# Motor-X.net
KiCad netlist of a schematic drawn in Altium Designer
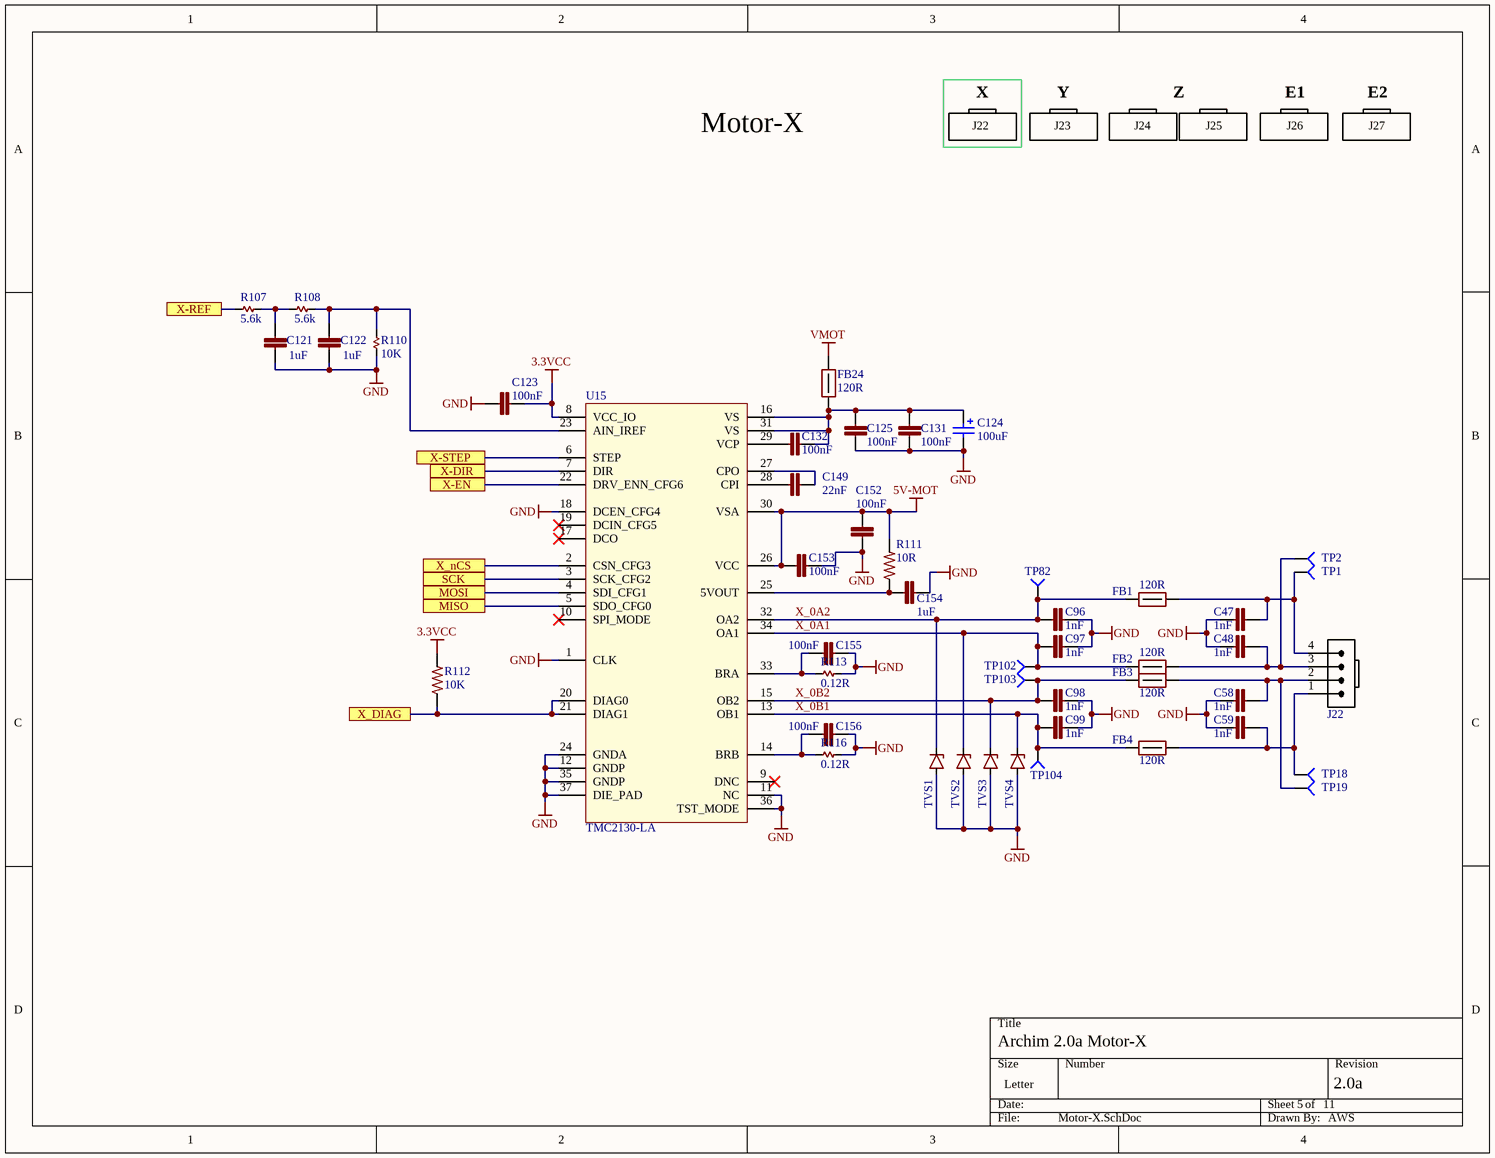
[diagram p0: Motor-X.SchDoc]

(export (version "E")
  (design (tool "Eeschema 10.0.6"))
  (components
    (comp (ref "C47")
      (value "1nF")
      (footprint "C0402")
      (description "1000pF 50V Ceramic Capacitor X7R 0402 (1005 Metric) 0.039\" L x 0.020\" W (1.00mm x 0.50mm)")
      (fields (field (name "MANUFACTURER") "Murata") (field (name "PART") "1nF 50V X7R 0402"))
      (libsource (lib "3Delight") (part "CAP 1nF 50V 0402 X7R"))
    )
    (comp (ref "C48")
      (value "1nF")
      (footprint "C0402")
      (description "1000pF 50V Ceramic Capacitor X7R 0402 (1005 Metric) 0.039\" L x 0.020\" W (1.00mm x 0.50mm)")
      (fields (field (name "MANUFACTURER") "Murata") (field (name "PART") "1nF 50V X7R 0402"))
      (libsource (lib "3Delight") (part "CAP 1nF 50V 0402 X7R"))
    )
    (comp (ref "C58")
      (value "1nF")
      (footprint "C0402")
      (description "1000pF 50V Ceramic Capacitor X7R 0402 (1005 Metric) 0.039\" L x 0.020\" W (1.00mm x 0.50mm)")
      (fields (field (name "MANUFACTURER") "Murata") (field (name "PART") "1nF 50V X7R 0402"))
      (libsource (lib "3Delight") (part "CAP 1nF 50V 0402 X7R"))
    )
    (comp (ref "C59")
      (value "1nF")
      (footprint "C0402")
      (description "1000pF 50V Ceramic Capacitor X7R 0402 (1005 Metric) 0.039\" L x 0.020\" W (1.00mm x 0.50mm)")
      (fields (field (name "MANUFACTURER") "Murata") (field (name "PART") "1nF 50V X7R 0402"))
      (libsource (lib "3Delight") (part "CAP 1nF 50V 0402 X7R"))
    )
    (comp (ref "C96")
      (value "1nF")
      (footprint "C0402")
      (description "1000pF 50V Ceramic Capacitor X7R 0402 (1005 Metric) 0.039\" L x 0.020\" W (1.00mm x 0.50mm)")
      (fields (field (name "MANUFACTURER") "Murata") (field (name "PART") "1nF 50V X7R 0402"))
      (libsource (lib "3Delight") (part "CAP 1nF 50V 0402 X7R"))
    )
    (comp (ref "C97")
      (value "1nF")
      (footprint "C0402")
      (description "1000pF 50V Ceramic Capacitor X7R 0402 (1005 Metric) 0.039\" L x 0.020\" W (1.00mm x 0.50mm)")
      (fields (field (name "MANUFACTURER") "Murata") (field (name "PART") "1nF 50V X7R 0402"))
      (libsource (lib "3Delight") (part "CAP 1nF 50V 0402 X7R"))
    )
    (comp (ref "C98")
      (value "1nF")
      (footprint "C0402")
      (description "1000pF 50V Ceramic Capacitor X7R 0402 (1005 Metric) 0.039\" L x 0.020\" W (1.00mm x 0.50mm)")
      (fields (field (name "MANUFACTURER") "Murata") (field (name "PART") "1nF 50V X7R 0402"))
      (libsource (lib "3Delight") (part "CAP 1nF 50V 0402 X7R"))
    )
    (comp (ref "C99")
      (value "1nF")
      (footprint "C0402")
      (description "1000pF 50V Ceramic Capacitor X7R 0402 (1005 Metric) 0.039\" L x 0.020\" W (1.00mm x 0.50mm)")
      (fields (field (name "MANUFACTURER") "Murata") (field (name "PART") "1nF 50V X7R 0402"))
      (libsource (lib "3Delight") (part "CAP 1nF 50V 0402 X7R"))
    )
    (comp (ref "C121")
      (value "1uF")
      (footprint "C0402")
      (description "CAP CER 0402 1uF 6.3V 10% X5R")
      (fields (field (name "MANUFACTURER") "Murata") (field (name "PART") "1uF 6.3V X5R 0402"))
      (libsource (lib "3Delight") (part "GRM155R60J105KE19D"))
    )
    (comp (ref "C122")
      (value "1uF")
      (footprint "C0402")
      (description "CAP CER 0402 1uF 6.3V 10% X5R")
      (fields (field (name "MANUFACTURER") "Murata") (field (name "PART") "1uF 6.3V X5R 0402"))
      (libsource (lib "3Delight") (part "GRM155R60J105KE19D"))
    )
    (comp (ref "C123")
      (value "100nF")
      (footprint "C0402")
      (description "CAP CER 0402 100nF 16V 10% X7R")
      (fields (field (name "MANUFACTURER") "Murata") (field (name "PART") "0.1uF 16V X7R 0402"))
      (libsource (lib "3Delight") (part "GRM155R71C104KA88D"))
    )
    (comp (ref "C124")
      (value "100uF")
      (footprint "CAP-ELEC-063063077")
      (description "CAP ALUM 100UF 35V 20% SMD")
      (fields (field (name "MANUFACTURER") "Nichicon") (field (name "PART") "100uF 35V SMD Al-El"))
      (libsource (lib "3Delight") (part "UWT1V101MCL1GS"))
    )
    (comp (ref "C125")
      (value "100nF")
      (footprint "C0603")
      (description "CAP CER 0603 100nF 50V 10% X7R")
      (fields (field (name "MANUFACTURER") "Kemet") (field (name "PART") "100nF 50V X7R 0603"))
      (libsource (lib "") (part "C0603C104K5RACTU_1"))
    )
    (comp (ref "C131")
      (value "100nF")
      (footprint "C0603")
      (description "CAP CER 0603 100nF 50V 10% X7R")
      (fields (field (name "MANUFACTURER") "Kemet") (field (name "PART") "100nF 50V X7R 0603"))
      (libsource (lib "") (part "C0603C104K5RACTU_1"))
    )
    (comp (ref "C132")
      (value "100nF")
      (footprint "C0603")
      (description "CAP CER 0603 100nF 50V 10% X7R")
      (fields (field (name "MANUFACTURER") "Kemet") (field (name "PART") "100nF 50V X7R 0603"))
      (libsource (lib "") (part "C0603C104K5RACTU_2"))
    )
    (comp (ref "C149")
      (value "22nF")
      (footprint "C0402")
      (description "CAP CER 0402 22nF ±10% 50V X7R")
      (fields (field (name "MANUFACTURER") "YAGEO") (field (name "TOLERANCE") "+/- 10%"))
      (libsource (lib "3Delight") (part "GCM155R71H223KA55D"))
    )
    (comp (ref "C152")
      (value "100nF")
      (footprint "C0402")
      (description "CAP CER 0402 100nF 16V 10% X7R")
      (fields (field (name "MANUFACTURER") "Murata") (field (name "PART") "0.1uF 16V X7R 0402"))
      (libsource (lib "") (part "GRM155R71C104KA88D_1"))
    )
    (comp (ref "C153")
      (value "100nF")
      (footprint "C0402")
      (description "CAP CER 0402 100nF 16V 10% X7R")
      (fields (field (name "MANUFACTURER") "Murata") (field (name "PART") "0.1uF 16V X7R 0402"))
      (libsource (lib "3Delight") (part "GRM155R71C104KA88D"))
    )
    (comp (ref "C154")
      (value "1uF")
      (footprint "C0402")
      (description "CAP CER 0402 1uF 6.3V 10% X5R")
      (fields (field (name "MANUFACTURER") "Murata") (field (name "PART") "1uF 6.3V X5R 0402"))
      (libsource (lib "") (part "GRM155R60J105KE19D_1"))
    )
    (comp (ref "C155")
      (value "100nF")
      (footprint "C0603")
      (description "CAP CER 0603 100nF 50V 10% X7R")
      (fields (field (name "MANUFACTURER") "Kemet") (field (name "PART") "100nF 50V X7R 0603"))
      (libsource (lib "3Delight") (part "C0603C104K5RACTU"))
    )
    (comp (ref "C156")
      (value "100nF")
      (footprint "C0603")
      (description "CAP CER 0603 100nF 50V 10% X7R")
      (fields (field (name "MANUFACTURER") "Kemet") (field (name "PART") "100nF 50V X7R 0603"))
      (libsource (lib "3Delight") (part "C0603C104K5RACTU"))
    )
    (comp (ref "FB1")
      (value "120R")
      (footprint "FB0603")
      (description "FERRITE BEAD 120 OHM 0603 1LN")
      (fields (field (name "MANUFACTURER") "Samsung") (field (name "PART") "FERRITE 120R 3A 0603"))
      (libsource (lib "3Delight") (part "FERRITE 220R 2.5A 0603"))
    )
    (comp (ref "FB2")
      (value "120R")
      (footprint "FB0603")
      (description "FERRITE BEAD 120 OHM 0603 1LN")
      (fields (field (name "MANUFACTURER") "Samsung") (field (name "PART") "FERRITE 120R 3A 0603"))
      (libsource (lib "3Delight") (part "FERRITE 220R 2.5A 0603"))
    )
    (comp (ref "FB3")
      (value "120R")
      (footprint "FB0603")
      (description "FERRITE BEAD 120 OHM 0603 1LN")
      (fields (field (name "MANUFACTURER") "Samsung") (field (name "PART") "FERRITE 120R 3A 0603"))
      (libsource (lib "3Delight") (part "FERRITE 220R 2.5A 0603"))
    )
    (comp (ref "FB4")
      (value "120R")
      (footprint "FB0603")
      (description "FERRITE BEAD 120 OHM 0603 1LN")
      (fields (field (name "MANUFACTURER") "Samsung") (field (name "PART") "FERRITE 120R 3A 0603"))
      (libsource (lib "3Delight") (part "FERRITE 220R 2.5A 0603"))
    )
    (comp (ref "FB24")
      (value "120R")
      (footprint "FB0603")
      (description "FERRITE BEAD 120 OHM 0603 1LN")
      (fields (field (name "MANUFACTURER") "Samsung") (field (name "PART") "FERRITE 120R 3A 0603"))
      (libsource (lib "Inductors") (part "FERRITE 120R 3A 0603"))
    )
    (comp (ref "J22")
      (value "Molex 0705430038")
      (footprint "4POL254 PIN-IN-PASTE")
      (description "Molex 4 Pin Clip Connector - Pin In Paste footprint")
      (libsource (lib "Connectors") (part "Molex 0705430003 PIP"))
    )
    (comp (ref "R107")
      (value "5.6k")
      (footprint "R0402")
      (description "RES SMD 5.6K OHM 1% 1/16W 0402")
      (fields (field (name "MANUFACTURER") "YAGEO") (field (name "TOLERANCE") "1%"))
      (libsource (lib "Resistors") (part "5.6k 1% 0402"))
    )
    (comp (ref "R108")
      (value "5.6k")
      (footprint "R0402")
      (description "RES SMD 5.6K OHM 1% 1/16W 0402")
      (fields (field (name "MANUFACTURER") "YAGEO") (field (name "TOLERANCE") "1%"))
      (libsource (lib "Resistors") (part "5.6k 1% 0402"))
    )
    (comp (ref "R110")
      (value "10K")
      (footprint "R0402")
      (description "RES SMD 10K OHM 1% 1/16W 0402")
      (fields (field (name "MANUFACTURER") "Yageo") (field (name "PART") "10k 1% 0402"))
      (libsource (lib "Resistors") (part "10k 1% 0402"))
    )
    (comp (ref "R111")
      (value "10R")
      (footprint "R0402")
      (description "RES SMD 10 OHM 1% 1/16W 0402")
      (fields (field (name "MANUFACTURER") "Yageo") (field (name "TOLERANCE") "1%"))
      (libsource (lib "3Delight") (part "RC0402FR-0710RL"))
    )
    (comp (ref "R112")
      (value "10K")
      (footprint "R0402")
      (description "RES SMD 10K OHM 1% 1/16W 0402")
      (fields (field (name "MANUFACTURER") "Yageo") (field (name "PART") "10k 1% 0402"))
      (libsource (lib "3Delight") (part "RC0402FR-0710KP"))
    )
    (comp (ref "R113")
      (value "0.12R")
      (footprint "R1206")
      (description "RES 0.12 OHM 1% 1/2W 1206")
      (fields (field (name "TOLERANCE") "+/- 1%"))
      (libsource (lib "Resistors") (part "0.12R 1% 1206"))
    )
    (comp (ref "R116")
      (value "0.12R")
      (footprint "R1206")
      (description "RES 0.12 OHM 1% 1/2W 1206")
      (fields (field (name "TOLERANCE") "+/- 1%"))
      (libsource (lib "Resistors") (part "0.12R 1% 1206"))
    )
    (comp (ref "TP1")
      (value "TP4")
      (footprint "TP-2")
      (description "Socket")
      (libsource (lib "Archim") (part "Socket"))
    )
    (comp (ref "TP2")
      (value "TP4")
      (footprint "TP-2")
      (description "Socket")
      (libsource (lib "Archim") (part "Socket"))
    )
    (comp (ref "TP18")
      (value "TP4")
      (footprint "TP-2")
      (description "Socket")
      (libsource (lib "Archim") (part "Socket"))
    )
    (comp (ref "TP19")
      (value "TP4")
      (footprint "TP-2")
      (description "Socket")
      (libsource (lib "Archim") (part "Socket"))
    )
    (comp (ref "TP82")
      (value "TP4")
      (footprint "TP-2")
      (description "Socket")
      (libsource (lib "Archim") (part "Socket"))
    )
    (comp (ref "TP102")
      (value "TP4")
      (footprint "TP-2")
      (description "Socket")
      (libsource (lib "Archim") (part "Socket"))
    )
    (comp (ref "TP103")
      (value "TP4")
      (footprint "TP-2")
      (description "Socket")
      (libsource (lib "Archim") (part "Socket"))
    )
    (comp (ref "TP104")
      (value "TP4")
      (footprint "TP-2")
      (description "Socket")
      (libsource (lib "Archim") (part "Socket"))
    )
    (comp (ref "TVS1")
      (value "TVS 30V SMF")
      (footprint "SMF")
      (description "TVS DIODE 30VWM 48.4VC SMF")
      (fields (field (name "MANUFACTURER") "Vishay") (field (name "PART") "TVS Diode 48.4VC"))
      (libsource (lib "3Delight") (part "TVS 30V SMF"))
    )
    (comp (ref "TVS2")
      (value "TVS 30V SMF")
      (footprint "SMF")
      (description "TVS DIODE 30VWM 48.4VC SMF")
      (fields (field (name "MANUFACTURER") "Vishay") (field (name "PART") "TVS Diode 48.4VC"))
      (libsource (lib "3Delight") (part "TVS 30V SMF"))
    )
    (comp (ref "TVS3")
      (value "TVS 30V SMF")
      (footprint "SMF")
      (description "TVS DIODE 30VWM 48.4VC SMF")
      (fields (field (name "MANUFACTURER") "Vishay") (field (name "PART") "TVS Diode 48.4VC"))
      (libsource (lib "3Delight") (part "TVS 30V SMF"))
    )
    (comp (ref "TVS4")
      (value "TVS 30V SMF")
      (footprint "SMF")
      (description "TVS DIODE 30VWM 48.4VC SMF")
      (fields (field (name "MANUFACTURER") "Vishay") (field (name "PART") "TVS Diode 48.4VC"))
      (libsource (lib "3Delight") (part "TVS 30V SMF"))
    )
    (comp (ref "U15")
      (value "TMC2130-LA")
      (footprint "QFN36-50P500X600X900_HS-37N")
      (description "IC STEPPER MOTOR DVR SPI 36QFN")
      (fields (field (name "MANUFACTURER") "Trinamic") (field (name "PART") "TMC2130"))
      (libsource (lib "ICs-Motor Controller") (part "TMC2130-LA-T"))
    )
  )
  (nets
    (net (code "1") (name "/MISO") (class "Default")
      (node (ref "U15") (pin "5") (pinfunction "SDO_CFG0_5") (pintype "passive"))
    )
    (net (code "2") (name "/MOSI") (class "Default")
      (node (ref "U15") (pin "4") (pinfunction "SDI_CFG1_4") (pintype "passive"))
    )
    (net (code "3") (name "/SCK") (class "Default")
      (node (ref "U15") (pin "3") (pinfunction "SCK_CFG2_3") (pintype "passive"))
    )
    (net (code "4") (name "/X-DIR") (class "Default")
      (node (ref "U15") (pin "7") (pinfunction "DIR_7") (pintype "passive"))
    )
    (net (code "5") (name "/X-EN") (class "Default")
      (node (ref "U15") (pin "22") (pinfunction "DRV_ENN_CFG6_22") (pintype "passive"))
    )
    (net (code "6") (name "/X-REF") (class "Default")
      (node (ref "R107") (pin "1") (pinfunction "1_1") (pintype "passive"))
    )
    (net (code "7") (name "/X-STEP") (class "Default")
      (node (ref "U15") (pin "6") (pinfunction "STEP_6") (pintype "passive"))
    )
    (net (code "8") (name "/X_0A1") (class "Default")
      (node (ref "C97") (pin "1") (pinfunction "1_1") (pintype "passive"))
      (node (ref "FB2") (pin "1") (pinfunction "1_1") (pintype "passive"))
      (node (ref "TP102") (pin "1") (pinfunction "1_1") (pintype "passive"))
      (node (ref "TVS2") (pin "K") (pinfunction "K_K") (pintype "passive"))
      (node (ref "U15") (pin "34") (pinfunction "OA1_34") (pintype "passive"))
    )
    (net (code "9") (name "/X_0A2") (class "Default")
      (node (ref "C96") (pin "1") (pinfunction "1_1") (pintype "passive"))
      (node (ref "FB1") (pin "1") (pinfunction "1_1") (pintype "passive"))
      (node (ref "TP82") (pin "1") (pinfunction "1_1") (pintype "passive"))
      (node (ref "TVS1") (pin "K") (pinfunction "K_K") (pintype "passive"))
      (node (ref "U15") (pin "32") (pinfunction "OA2_32") (pintype "passive"))
    )
    (net (code "10") (name "/X_0B1") (class "Default")
      (node (ref "C99") (pin "1") (pinfunction "1_1") (pintype "passive"))
      (node (ref "FB4") (pin "1") (pinfunction "1_1") (pintype "passive"))
      (node (ref "TP104") (pin "1") (pinfunction "1_1") (pintype "passive"))
      (node (ref "TVS4") (pin "K") (pinfunction "K_K") (pintype "passive"))
      (node (ref "U15") (pin "13") (pinfunction "OB1_13") (pintype "passive"))
    )
    (net (code "11") (name "/X_0B2") (class "Default")
      (node (ref "C98") (pin "1") (pinfunction "1_1") (pintype "passive"))
      (node (ref "FB3") (pin "1") (pinfunction "1_1") (pintype "passive"))
      (node (ref "TP103") (pin "1") (pinfunction "1_1") (pintype "passive"))
      (node (ref "TVS3") (pin "K") (pinfunction "K_K") (pintype "passive"))
      (node (ref "U15") (pin "15") (pinfunction "OB2_15") (pintype "passive"))
    )
    (net (code "12") (name "/X_DIAG") (class "Default")
      (node (ref "R112") (pin "1") (pinfunction "1_1") (pintype "passive"))
      (node (ref "U15") (pin "20") (pinfunction "DIAG0_20") (pintype "passive"))
      (node (ref "U15") (pin "21") (pinfunction "DIAG1_21") (pintype "passive"))
    )
    (net (code "13") (name "/X_nCS") (class "Default")
      (node (ref "U15") (pin "2") (pinfunction "CSN_CFG3_2") (pintype "passive"))
    )
    (net (code "14") (name "3.3VCC") (class "Default")
      (node (ref "C123") (pin "1") (pinfunction "1_1") (pintype "passive"))
      (node (ref "R112") (pin "2") (pinfunction "2_2") (pintype "passive"))
      (node (ref "U15") (pin "8") (pinfunction "VCC_IO_8") (pintype "passive"))
    )
    (net (code "15") (name "5V-MOT") (class "Default")
      (node (ref "C152") (pin "2") (pinfunction "2_2") (pintype "passive"))
      (node (ref "C153") (pin "2") (pinfunction "2_2") (pintype "passive"))
      (node (ref "R111") (pin "2") (pinfunction "2_2") (pintype "passive"))
      (node (ref "U15") (pin "26") (pinfunction "VCC_26") (pintype "passive"))
      (node (ref "U15") (pin "30") (pinfunction "VSA_30") (pintype "passive"))
    )
    (net (code "16") (name "GND") (class "Default")
      (node (ref "C121") (pin "2") (pinfunction "2_2") (pintype "passive"))
      (node (ref "C122") (pin "2") (pinfunction "2_2") (pintype "passive"))
      (node (ref "C123") (pin "2") (pinfunction "2_2") (pintype "passive"))
      (node (ref "C124") (pin "2") (pinfunction "2_2") (pintype "passive"))
      (node (ref "C125") (pin "1") (pinfunction "1_1") (pintype "passive"))
      (node (ref "C131") (pin "1") (pinfunction "1_1") (pintype "passive"))
      (node (ref "C152") (pin "1") (pinfunction "1_1") (pintype "passive"))
      (node (ref "C153") (pin "1") (pinfunction "1_1") (pintype "passive"))
      (node (ref "C154") (pin "2") (pinfunction "2_2") (pintype "passive"))
      (node (ref "C155") (pin "1") (pinfunction "1_1") (pintype "passive"))
      (node (ref "C156") (pin "1") (pinfunction "1_1") (pintype "passive"))
      (node (ref "C47") (pin "1") (pinfunction "1_1") (pintype "passive"))
      (node (ref "C48") (pin "1") (pinfunction "1_1") (pintype "passive"))
      (node (ref "C58") (pin "1") (pinfunction "1_1") (pintype "passive"))
      (node (ref "C59") (pin "1") (pinfunction "1_1") (pintype "passive"))
      (node (ref "C96") (pin "2") (pinfunction "2_2") (pintype "passive"))
      (node (ref "C97") (pin "2") (pinfunction "2_2") (pintype "passive"))
      (node (ref "C98") (pin "2") (pinfunction "2_2") (pintype "passive"))
      (node (ref "C99") (pin "2") (pinfunction "2_2") (pintype "passive"))
      (node (ref "R110") (pin "1") (pinfunction "1_1") (pintype "passive"))
      (node (ref "R113") (pin "2") (pinfunction "2_2") (pintype "passive"))
      (node (ref "R116") (pin "2") (pinfunction "2_2") (pintype "passive"))
      (node (ref "TVS1") (pin "A") (pinfunction "A_A") (pintype "passive"))
      (node (ref "TVS2") (pin "A") (pinfunction "A_A") (pintype "passive"))
      (node (ref "TVS3") (pin "A") (pinfunction "A_A") (pintype "passive"))
      (node (ref "TVS4") (pin "A") (pinfunction "A_A") (pintype "passive"))
      (node (ref "U15") (pin "1") (pinfunction "CLK_1") (pintype "passive"))
      (node (ref "U15") (pin "11") (pinfunction "NC_11") (pintype "passive"))
      (node (ref "U15") (pin "12") (pinfunction "GNDP_12") (pintype "passive"))
      (node (ref "U15") (pin "18") (pinfunction "DCEN_CFG4_18") (pintype "passive"))
      (node (ref "U15") (pin "24") (pinfunction "GNDA_24") (pintype "passive"))
      (node (ref "U15") (pin "35") (pinfunction "GNDP_35") (pintype "passive"))
      (node (ref "U15") (pin "36") (pinfunction "TST_MODE_36") (pintype "passive"))
      (node (ref "U15") (pin "37") (pinfunction "DIE_PAD_37") (pintype "passive"))
    )
    (net (code "17") (name "Net-(C47-Pad2)") (class "Default")
      (node (ref "C47") (pin "2") (pinfunction "2_2") (pintype "passive"))
      (node (ref "FB1") (pin "2") (pinfunction "2_2") (pintype "passive"))
      (node (ref "J22") (pin "4") (pinfunction "4_4") (pintype "passive"))
      (node (ref "TP1") (pin "1") (pinfunction "1_1") (pintype "passive"))
    )
    (net (code "18") (name "Net-(C48-Pad2)") (class "Default")
      (node (ref "C48") (pin "2") (pinfunction "2_2") (pintype "passive"))
      (node (ref "FB2") (pin "2") (pinfunction "2_2") (pintype "passive"))
      (node (ref "J22") (pin "3") (pinfunction "3_3") (pintype "passive"))
      (node (ref "TP2") (pin "1") (pinfunction "1_1") (pintype "passive"))
    )
    (net (code "19") (name "Net-(C58-Pad2)") (class "Default")
      (node (ref "C58") (pin "2") (pinfunction "2_2") (pintype "passive"))
      (node (ref "FB3") (pin "2") (pinfunction "2_2") (pintype "passive"))
      (node (ref "J22") (pin "2") (pinfunction "2_2") (pintype "passive"))
      (node (ref "TP19") (pin "1") (pinfunction "1_1") (pintype "passive"))
    )
    (net (code "20") (name "Net-(C59-Pad2)") (class "Default")
      (node (ref "C59") (pin "2") (pinfunction "2_2") (pintype "passive"))
      (node (ref "FB4") (pin "2") (pinfunction "2_2") (pintype "passive"))
      (node (ref "J22") (pin "1") (pinfunction "1_1") (pintype "passive"))
      (node (ref "TP18") (pin "1") (pinfunction "1_1") (pintype "passive"))
    )
    (net (code "21") (name "Net-(C121-Pad1)") (class "Default")
      (node (ref "C121") (pin "1") (pinfunction "1_1") (pintype "passive"))
      (node (ref "R107") (pin "2") (pinfunction "2_2") (pintype "passive"))
      (node (ref "R108") (pin "1") (pinfunction "1_1") (pintype "passive"))
    )
    (net (code "22") (name "Net-(C124-Pad1)") (class "Default")
      (node (ref "C124") (pin "1") (pinfunction "1_1") (pintype "passive"))
      (node (ref "C125") (pin "2") (pinfunction "2_2") (pintype "passive"))
      (node (ref "C131") (pin "2") (pinfunction "2_2") (pintype "passive"))
      (node (ref "C132") (pin "2") (pinfunction "2_2") (pintype "passive"))
      (node (ref "FB24") (pin "1") (pinfunction "1_1") (pintype "passive"))
      (node (ref "U15") (pin "16") (pinfunction "VS_16") (pintype "passive"))
      (node (ref "U15") (pin "31") (pinfunction "VS_31") (pintype "passive"))
    )
    (net (code "23") (name "Net-(U15-5VOUT)") (class "Default")
      (node (ref "C154") (pin "1") (pinfunction "1_1") (pintype "passive"))
      (node (ref "R111") (pin "1") (pinfunction "1_1") (pintype "passive"))
      (node (ref "U15") (pin "25") (pinfunction "5VOUT_25") (pintype "passive"))
    )
    (net (code "24") (name "Net-(U15-AIN_IREF)") (class "Default")
      (node (ref "C122") (pin "1") (pinfunction "1_1") (pintype "passive"))
      (node (ref "R108") (pin "2") (pinfunction "2_2") (pintype "passive"))
      (node (ref "R110") (pin "2") (pinfunction "2_2") (pintype "passive"))
      (node (ref "U15") (pin "23") (pinfunction "AIN_IREF_23") (pintype "passive"))
    )
    (net (code "25") (name "Net-(U15-BRA)") (class "Default")
      (node (ref "C155") (pin "2") (pinfunction "2_2") (pintype "passive"))
      (node (ref "R113") (pin "1") (pinfunction "1_1") (pintype "passive"))
      (node (ref "U15") (pin "33") (pinfunction "BRA_33") (pintype "passive"))
    )
    (net (code "26") (name "Net-(U15-BRB)") (class "Default")
      (node (ref "C156") (pin "2") (pinfunction "2_2") (pintype "passive"))
      (node (ref "R116") (pin "1") (pinfunction "1_1") (pintype "passive"))
      (node (ref "U15") (pin "14") (pinfunction "BRB_14") (pintype "passive"))
    )
    (net (code "27") (name "Net-(U15-CPI)") (class "Default")
      (node (ref "C149") (pin "1") (pinfunction "1_1") (pintype "passive"))
      (node (ref "U15") (pin "28") (pinfunction "CPI_28") (pintype "passive"))
    )
    (net (code "28") (name "Net-(U15-CPO)") (class "Default")
      (node (ref "C149") (pin "2") (pinfunction "2_2") (pintype "passive"))
      (node (ref "U15") (pin "27") (pinfunction "CPO_27") (pintype "passive"))
    )
    (net (code "29") (name "Net-(U15-VCP)") (class "Default")
      (node (ref "C132") (pin "1") (pinfunction "1_1") (pintype "passive"))
      (node (ref "U15") (pin "29") (pinfunction "VCP_29") (pintype "passive"))
    )
    (net (code "30") (name "VMOT") (class "Default")
      (node (ref "FB24") (pin "2") (pinfunction "2_2") (pintype "passive"))
    )
    (net (code "31") (name "unconnected-(U15-DCIN_CFG5-Pad19)") (class "Default")
      (node (ref "U15") (pin "19") (pinfunction "DCIN_CFG5_19") (pintype "passive+no_connect"))
    )
    (net (code "32") (name "unconnected-(U15-DCO-Pad17)") (class "Default")
      (node (ref "U15") (pin "17") (pinfunction "DCO_17") (pintype "passive+no_connect"))
    )
    (net (code "33") (name "unconnected-(U15-DNC-Pad9)") (class "Default")
      (node (ref "U15") (pin "9") (pinfunction "DNC_9") (pintype "passive+no_connect"))
    )
    (net (code "34") (name "unconnected-(U15-SPI_MODE-Pad10)") (class "Default")
      (node (ref "U15") (pin "10") (pinfunction "SPI_MODE_10") (pintype "passive+no_connect"))
    )
  )
)
